# SCH_TRINIT_BYTE-HOGS_IOT_2023-02-12.net
KiCad netlist of a schematic drawn in EasyEDA
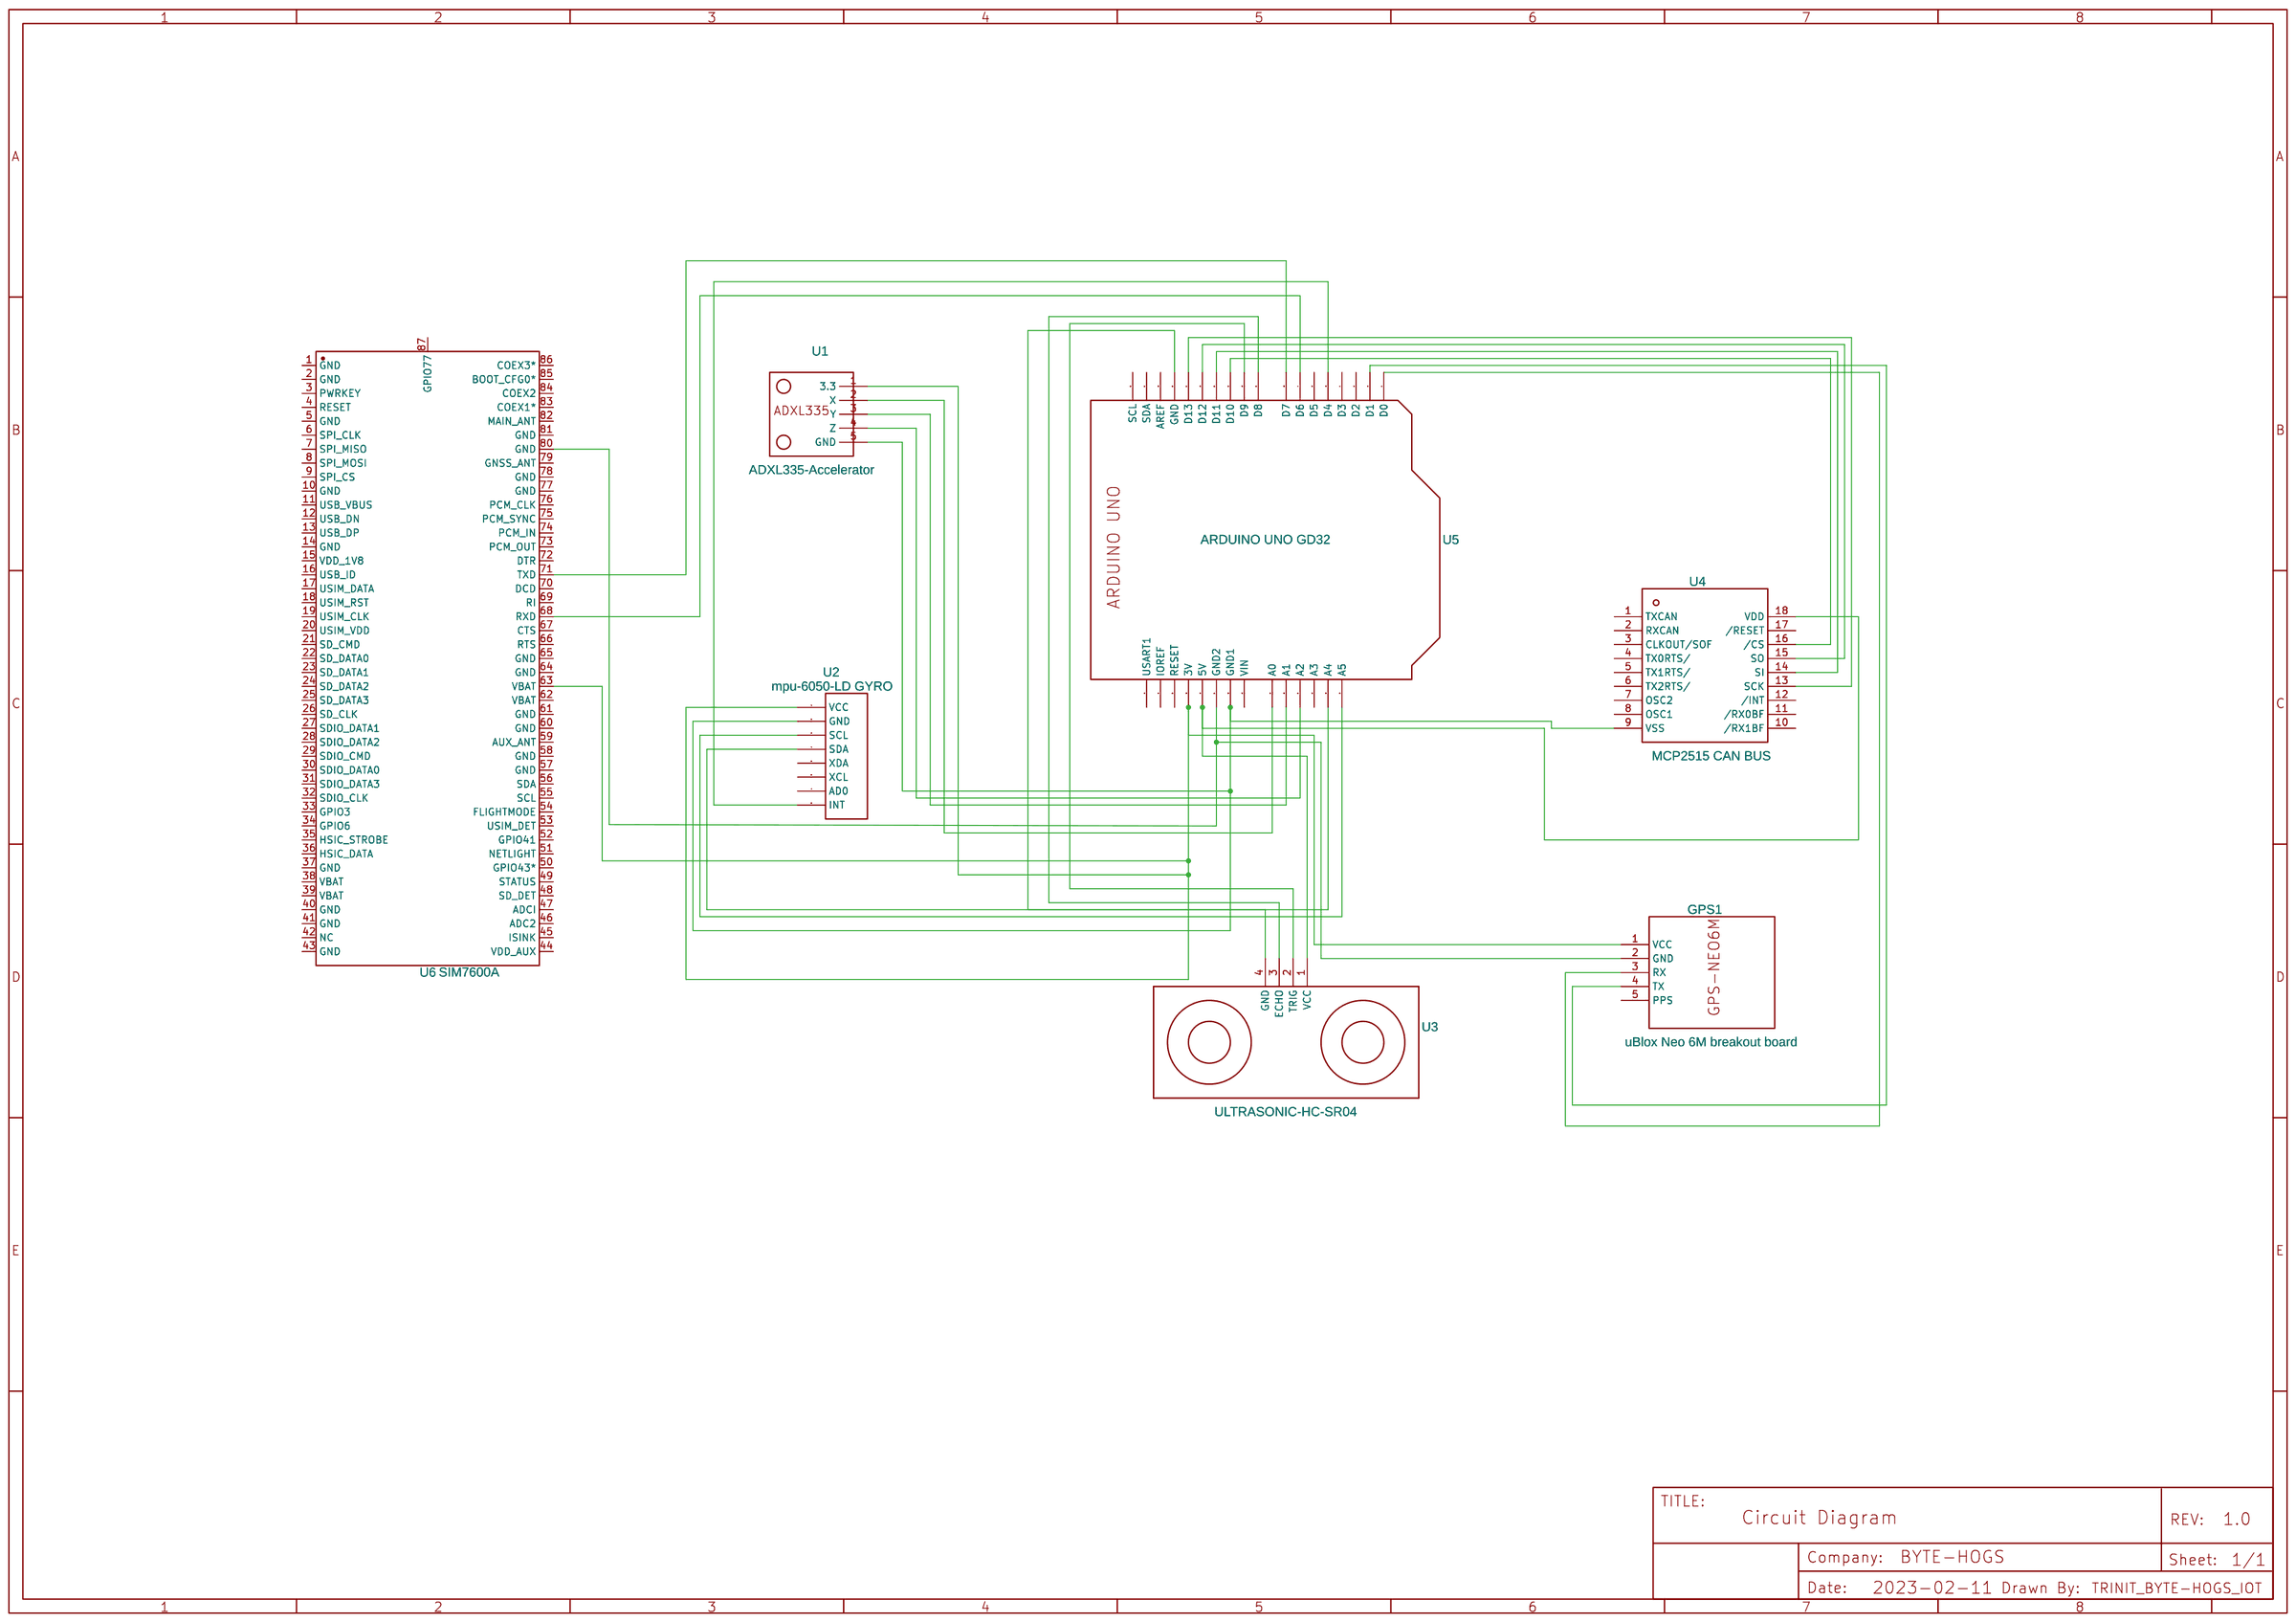
[diagram p0: schematic sheet]

(export (version "E")
  (design (tool "Eeschema 10.0.6"))
  (components
    (comp (ref "GPS1")
      (value "uBlox Neo 6M breakout board")
      (fields
        (field (name "BOM_Manufacturer Part") "GY-NEO6M")
        (field (name "BOM_Supplier Part") "GY-NEO6MV2")
      )
      (libsource (lib "") (part "uBlox Neo 6M breakout board"))
    )
    (comp (ref "U1")
      (value "ADXL335-Accelerator")
      (fields (field (name "BOM_Manufacturer Part") "ADXL335"))
      (libsource (lib "") (part "ADXL335"))
    )
    (comp (ref "U2") (value "mpu-6050-LD GYRO") (libsource (lib "") (part "mpu-6050-LD")))
    (comp (ref "U3") (value "ULTRASONIC-HC-SR04") (libsource (lib "") (part "ULTRASONIC-HC-SR04")))
    (comp (ref "U4") (value "MCP2515 CAN BUS") (libsource (lib "") (part "MCP2515 COPY")))
    (comp (ref "U5") (value "ARDUINO UNO GD32") (libsource (lib "") (part "ARDUINO UNO GD32")))
    (comp (ref "U6")
      (value "SIM7600A")
      (fields (field (name "BOM_Supplier Part") "C2995537"))
      (libsource (lib "") (part "SIM7600A"))
    )
  )
  (nets
    (net (code "1") (name "Net-(GPS1-GND)") (class "Default")
      (node (ref "GPS1") (pin "2") (pinfunction "GND_2") (pintype "unspecified"))
      (node (ref "U5") (pin "27") (pinfunction "GND2_27") (pintype "passive"))
      (node (ref "U6") (pin "80") (pinfunction "GND_80") (pintype "unspecified"))
    )
    (net (code "2") (name "Net-(GPS1-RX)") (class "Default")
      (node (ref "GPS1") (pin "3") (pinfunction "RX_3") (pintype "unspecified"))
      (node (ref "U5") (pin "1") (pinfunction "D0_1") (pintype "unspecified"))
    )
    (net (code "3") (name "Net-(GPS1-TX)") (class "Default")
      (node (ref "GPS1") (pin "4") (pinfunction "TX_4") (pintype "unspecified"))
      (node (ref "U5") (pin "2") (pinfunction "D1_2") (pintype "unspecified"))
    )
    (net (code "4") (name "Net-(GPS1-VCC)") (class "Default")
      (node (ref "GPS1") (pin "1") (pinfunction "VCC_1") (pintype "unspecified"))
      (node (ref "U1") (pin "1") (pinfunction "3.3_1") (pintype "unspecified"))
      (node (ref "U2") (pin "1") (pinfunction "VCC_1") (pintype "unspecified"))
      (node (ref "U5") (pin "29") (pinfunction "3V_29") (pintype "passive"))
      (node (ref "U6") (pin "63") (pinfunction "VBAT_63") (pintype "unspecified"))
    )
    (net (code "5") (name "Net-(U1-GND)") (class "Default")
      (node (ref "U1") (pin "5") (pinfunction "GND_5") (pintype "unspecified"))
      (node (ref "U2") (pin "2") (pinfunction "GND_2") (pintype "unspecified"))
      (node (ref "U4") (pin "9") (pinfunction "VSS_9") (pintype "unspecified"))
      (node (ref "U5") (pin "26") (pinfunction "GND1_26") (pintype "passive"))
    )
    (net (code "6") (name "Net-(U1-X)") (class "Default")
      (node (ref "U1") (pin "2") (pinfunction "X_2") (pintype "unspecified"))
      (node (ref "U5") (pin "24") (pinfunction "A0_24") (pintype "unspecified"))
    )
    (net (code "7") (name "Net-(U1-Y)") (class "Default")
      (node (ref "U1") (pin "3") (pinfunction "Y_3") (pintype "unspecified"))
      (node (ref "U5") (pin "23") (pinfunction "A1_23") (pintype "unspecified"))
    )
    (net (code "8") (name "Net-(U1-Z)") (class "Default")
      (node (ref "U1") (pin "4") (pinfunction "Z_4") (pintype "unspecified"))
      (node (ref "U5") (pin "22") (pinfunction "A2_22") (pintype "unspecified"))
    )
    (net (code "9") (name "Net-(U2-INT)") (class "Default")
      (node (ref "U2") (pin "8") (pinfunction "INT_8") (pintype "unspecified"))
      (node (ref "U5") (pin "5") (pinfunction "D4_5") (pintype "unspecified"))
    )
    (net (code "10") (name "Net-(U2-SCL)") (class "Default")
      (node (ref "U2") (pin "3") (pinfunction "SCL_3") (pintype "unspecified"))
      (node (ref "U5") (pin "19") (pinfunction "A5_19") (pintype "unspecified"))
    )
    (net (code "11") (name "Net-(U2-SDA)") (class "Default")
      (node (ref "U2") (pin "4") (pinfunction "SDA_4") (pintype "unspecified"))
      (node (ref "U5") (pin "20") (pinfunction "A4_20") (pintype "unspecified"))
    )
    (net (code "12") (name "Net-(U3-ECHO)") (class "Default")
      (node (ref "U3") (pin "3") (pinfunction "ECHO_3") (pintype "output"))
      (node (ref "U5") (pin "9") (pinfunction "D8_9") (pintype "unspecified"))
    )
    (net (code "13") (name "Net-(U3-GND)") (class "Default")
      (node (ref "U3") (pin "4") (pinfunction "GND_4") (pintype "passive"))
      (node (ref "U5") (pin "15") (pinfunction "GND_15") (pintype "passive"))
    )
    (net (code "14") (name "Net-(U3-TRIG)") (class "Default")
      (node (ref "U3") (pin "2") (pinfunction "TRIG_2") (pintype "input"))
      (node (ref "U5") (pin "10") (pinfunction "D9_10") (pintype "unspecified"))
    )
    (net (code "15") (name "Net-(U3-VCC)") (class "Default")
      (node (ref "U3") (pin "1") (pinfunction "VCC_1") (pintype "passive"))
      (node (ref "U4") (pin "18") (pinfunction "VDD_18") (pintype "unspecified"))
      (node (ref "U5") (pin "28") (pinfunction "5V_28") (pintype "passive"))
    )
    (net (code "16") (name "Net-(U4-SCK)") (class "Default")
      (node (ref "U4") (pin "13") (pinfunction "SCK_13") (pintype "unspecified"))
      (node (ref "U5") (pin "14") (pinfunction "D13_14") (pintype "unspecified"))
    )
    (net (code "17") (name "Net-(U4-SI)") (class "Default")
      (node (ref "U4") (pin "14") (pinfunction "SI_14") (pintype "unspecified"))
      (node (ref "U5") (pin "12") (pinfunction "D11_12") (pintype "unspecified"))
    )
    (net (code "18") (name "Net-(U4-SO)") (class "Default")
      (node (ref "U4") (pin "15") (pinfunction "SO_15") (pintype "unspecified"))
      (node (ref "U5") (pin "13") (pinfunction "D12_13") (pintype "unspecified"))
    )
    (net (code "19") (name "Net-(U4-{slash}CS)") (class "Default")
      (node (ref "U4") (pin "16") (pinfunction "/CS_16") (pintype "unspecified"))
      (node (ref "U5") (pin "11") (pinfunction "D10_11") (pintype "unspecified"))
    )
    (net (code "20") (name "Net-(U5-D6)") (class "Default")
      (node (ref "U5") (pin "7") (pinfunction "D6_7") (pintype "unspecified"))
      (node (ref "U6") (pin "68") (pinfunction "RXD_68") (pintype "unspecified"))
    )
    (net (code "21") (name "Net-(U5-D7)") (class "Default")
      (node (ref "U5") (pin "8") (pinfunction "D7_8") (pintype "unspecified"))
      (node (ref "U6") (pin "71") (pinfunction "TXD_71") (pintype "unspecified"))
    )
    (net (code "22") (name "unconnected-(GPS1-PPS-Pad5)") (class "Default")
      (node (ref "GPS1") (pin "5") (pinfunction "PPS_5") (pintype "unspecified"))
    )
    (net (code "23") (name "unconnected-(U2-AD0-Pad7)") (class "Default")
      (node (ref "U2") (pin "7") (pinfunction "AD0_7") (pintype "unspecified"))
    )
    (net (code "24") (name "unconnected-(U2-XCL-Pad6)") (class "Default")
      (node (ref "U2") (pin "6") (pinfunction "XCL_6") (pintype "unspecified"))
    )
    (net (code "25") (name "unconnected-(U2-XDA-Pad5)") (class "Default")
      (node (ref "U2") (pin "5") (pinfunction "XDA_5") (pintype "unspecified"))
    )
    (net (code "26") (name "unconnected-(U4-CLKOUT{slash}SOF-Pad3)") (class "Default")
      (node (ref "U4") (pin "3") (pinfunction "CLKOUT/SOF_3") (pintype "unspecified"))
    )
    (net (code "27") (name "unconnected-(U4-OSC1-Pad8)") (class "Default")
      (node (ref "U4") (pin "8") (pinfunction "OSC1_8") (pintype "unspecified"))
    )
    (net (code "28") (name "unconnected-(U4-OSC2-Pad7)") (class "Default")
      (node (ref "U4") (pin "7") (pinfunction "OSC2_7") (pintype "unspecified"))
    )
    (net (code "29") (name "unconnected-(U4-RXCAN-Pad2)") (class "Default")
      (node (ref "U4") (pin "2") (pinfunction "RXCAN_2") (pintype "unspecified"))
    )
    (net (code "30") (name "unconnected-(U4-TX0RTS{slash}-Pad4)") (class "Default")
      (node (ref "U4") (pin "4") (pinfunction "TX0RTS/_4") (pintype "unspecified"))
    )
    (net (code "31") (name "unconnected-(U4-TX1RTS{slash}-Pad5)") (class "Default")
      (node (ref "U4") (pin "5") (pinfunction "TX1RTS/_5") (pintype "unspecified"))
    )
    (net (code "32") (name "unconnected-(U4-TX2RTS{slash}-Pad6)") (class "Default")
      (node (ref "U4") (pin "6") (pinfunction "TX2RTS/_6") (pintype "unspecified"))
    )
    (net (code "33") (name "unconnected-(U4-TXCAN-Pad1)") (class "Default")
      (node (ref "U4") (pin "1") (pinfunction "TXCAN_1") (pintype "unspecified"))
    )
    (net (code "34") (name "unconnected-(U4-{slash}INT-Pad12)") (class "Default")
      (node (ref "U4") (pin "12") (pinfunction "/INT_12") (pintype "unspecified"))
    )
    (net (code "35") (name "unconnected-(U4-{slash}RESET-Pad17)") (class "Default")
      (node (ref "U4") (pin "17") (pinfunction "/RESET_17") (pintype "unspecified"))
    )
    (net (code "36") (name "unconnected-(U4-{slash}RX0BF-Pad11)") (class "Default")
      (node (ref "U4") (pin "11") (pinfunction "/RX0BF_11") (pintype "unspecified"))
    )
    (net (code "37") (name "unconnected-(U4-{slash}RX1BF-Pad10)") (class "Default")
      (node (ref "U4") (pin "10") (pinfunction "/RX1BF_10") (pintype "unspecified"))
    )
    (net (code "38") (name "unconnected-(U5-A3-Pad21)") (class "Default")
      (node (ref "U5") (pin "21") (pinfunction "A3_21") (pintype "unspecified"))
    )
    (net (code "39") (name "unconnected-(U5-AREF-Pad16)") (class "Default")
      (node (ref "U5") (pin "16") (pinfunction "AREF_16") (pintype "unspecified"))
    )
    (net (code "40") (name "unconnected-(U5-D2-Pad3)") (class "Default")
      (node (ref "U5") (pin "3") (pinfunction "D2_3") (pintype "unspecified"))
    )
    (net (code "41") (name "unconnected-(U5-D3-Pad4)") (class "Default")
      (node (ref "U5") (pin "4") (pinfunction "D3_4") (pintype "unspecified"))
    )
    (net (code "42") (name "unconnected-(U5-D5-Pad6)") (class "Default")
      (node (ref "U5") (pin "6") (pinfunction "D5_6") (pintype "unspecified"))
    )
    (net (code "43") (name "unconnected-(U5-IOREF-Pad31)") (class "Default")
      (node (ref "U5") (pin "31") (pinfunction "IOREF_31") (pintype "unspecified"))
    )
    (net (code "44") (name "unconnected-(U5-RESET-Pad30)") (class "Default")
      (node (ref "U5") (pin "30") (pinfunction "RESET_30") (pintype "unspecified"))
    )
    (net (code "45") (name "unconnected-(U5-SCL-Pad18)") (class "Default")
      (node (ref "U5") (pin "18") (pinfunction "SCL_18") (pintype "unspecified"))
    )
    (net (code "46") (name "unconnected-(U5-SDA-Pad17)") (class "Default")
      (node (ref "U5") (pin "17") (pinfunction "SDA_17") (pintype "unspecified"))
    )
    (net (code "47") (name "unconnected-(U5-USART1-Pad32)") (class "Default")
      (node (ref "U5") (pin "32") (pinfunction "USART1_32") (pintype "unspecified"))
    )
    (net (code "48") (name "unconnected-(U5-VIN-Pad25)") (class "Default")
      (node (ref "U5") (pin "25") (pinfunction "VIN_25") (pintype "passive"))
    )
    (net (code "49") (name "unconnected-(U6-ADC2-Pad46)") (class "Default")
      (node (ref "U6") (pin "46") (pinfunction "ADC2_46") (pintype "unspecified"))
    )
    (net (code "50") (name "unconnected-(U6-ADCI-Pad47)") (class "Default")
      (node (ref "U6") (pin "47") (pinfunction "ADCI_47") (pintype "unspecified"))
    )
    (net (code "51") (name "unconnected-(U6-AUX_ANT-Pad59)") (class "Default")
      (node (ref "U6") (pin "59") (pinfunction "AUX_ANT_59") (pintype "unspecified"))
    )
    (net (code "52") (name "unconnected-(U6-BOOT_CFG0*-Pad85)") (class "Default")
      (node (ref "U6") (pin "85") (pinfunction "BOOT_CFG0*_85") (pintype "unspecified"))
    )
    (net (code "53") (name "unconnected-(U6-COEX1*-Pad83)") (class "Default")
      (node (ref "U6") (pin "83") (pinfunction "COEX1*_83") (pintype "unspecified"))
    )
    (net (code "54") (name "unconnected-(U6-COEX2-Pad84)") (class "Default")
      (node (ref "U6") (pin "84") (pinfunction "COEX2_84") (pintype "unspecified"))
    )
    (net (code "55") (name "unconnected-(U6-COEX3*-Pad86)") (class "Default")
      (node (ref "U6") (pin "86") (pinfunction "COEX3*_86") (pintype "unspecified"))
    )
    (net (code "56") (name "unconnected-(U6-CTS-Pad67)") (class "Default")
      (node (ref "U6") (pin "67") (pinfunction "CTS_67") (pintype "unspecified"))
    )
    (net (code "57") (name "unconnected-(U6-DCD-Pad70)") (class "Default")
      (node (ref "U6") (pin "70") (pinfunction "DCD_70") (pintype "unspecified"))
    )
    (net (code "58") (name "unconnected-(U6-DTR-Pad72)") (class "Default")
      (node (ref "U6") (pin "72") (pinfunction "DTR_72") (pintype "unspecified"))
    )
    (net (code "59") (name "unconnected-(U6-FLIGHTMODE-Pad54)") (class "Default")
      (node (ref "U6") (pin "54") (pinfunction "FLIGHTMODE_54") (pintype "unspecified"))
    )
    (net (code "60") (name "unconnected-(U6-GND-Pad1)") (class "Default")
      (node (ref "U6") (pin "1") (pinfunction "GND_1") (pintype "unspecified"))
    )
    (net (code "61") (name "unconnected-(U6-GND-Pad2)") (class "Default")
      (node (ref "U6") (pin "2") (pinfunction "GND_2") (pintype "unspecified"))
    )
    (net (code "62") (name "unconnected-(U6-GND-Pad5)") (class "Default")
      (node (ref "U6") (pin "5") (pinfunction "GND_5") (pintype "unspecified"))
    )
    (net (code "63") (name "unconnected-(U6-GND-Pad10)") (class "Default")
      (node (ref "U6") (pin "10") (pinfunction "GND_10") (pintype "unspecified"))
    )
    (net (code "64") (name "unconnected-(U6-GND-Pad14)") (class "Default")
      (node (ref "U6") (pin "14") (pinfunction "GND_14") (pintype "unspecified"))
    )
    (net (code "65") (name "unconnected-(U6-GND-Pad37)") (class "Default")
      (node (ref "U6") (pin "37") (pinfunction "GND_37") (pintype "unspecified"))
    )
    (net (code "66") (name "unconnected-(U6-GND-Pad40)") (class "Default")
      (node (ref "U6") (pin "40") (pinfunction "GND_40") (pintype "unspecified"))
    )
    (net (code "67") (name "unconnected-(U6-GND-Pad41)") (class "Default")
      (node (ref "U6") (pin "41") (pinfunction "GND_41") (pintype "unspecified"))
    )
    (net (code "68") (name "unconnected-(U6-GND-Pad43)") (class "Default")
      (node (ref "U6") (pin "43") (pinfunction "GND_43") (pintype "unspecified"))
    )
    (net (code "69") (name "unconnected-(U6-GND-Pad57)") (class "Default")
      (node (ref "U6") (pin "57") (pinfunction "GND_57") (pintype "unspecified"))
    )
    (net (code "70") (name "unconnected-(U6-GND-Pad58)") (class "Default")
      (node (ref "U6") (pin "58") (pinfunction "GND_58") (pintype "unspecified"))
    )
    (net (code "71") (name "unconnected-(U6-GND-Pad60)") (class "Default")
      (node (ref "U6") (pin "60") (pinfunction "GND_60") (pintype "unspecified"))
    )
    (net (code "72") (name "unconnected-(U6-GND-Pad61)") (class "Default")
      (node (ref "U6") (pin "61") (pinfunction "GND_61") (pintype "unspecified"))
    )
    (net (code "73") (name "unconnected-(U6-GND-Pad64)") (class "Default")
      (node (ref "U6") (pin "64") (pinfunction "GND_64") (pintype "unspecified"))
    )
    (net (code "74") (name "unconnected-(U6-GND-Pad65)") (class "Default")
      (node (ref "U6") (pin "65") (pinfunction "GND_65") (pintype "unspecified"))
    )
    (net (code "75") (name "unconnected-(U6-GND-Pad77)") (class "Default")
      (node (ref "U6") (pin "77") (pinfunction "GND_77") (pintype "unspecified"))
    )
    (net (code "76") (name "unconnected-(U6-GND-Pad78)") (class "Default")
      (node (ref "U6") (pin "78") (pinfunction "GND_78") (pintype "unspecified"))
    )
    (net (code "77") (name "unconnected-(U6-GND-Pad81)") (class "Default")
      (node (ref "U6") (pin "81") (pinfunction "GND_81") (pintype "unspecified"))
    )
    (net (code "78") (name "unconnected-(U6-GNSS_ANT-Pad79)") (class "Default")
      (node (ref "U6") (pin "79") (pinfunction "GNSS_ANT_79") (pintype "unspecified"))
    )
    (net (code "79") (name "unconnected-(U6-GPIO3-Pad33)") (class "Default")
      (node (ref "U6") (pin "33") (pinfunction "GPIO3_33") (pintype "unspecified"))
    )
    (net (code "80") (name "unconnected-(U6-GPIO6-Pad34)") (class "Default")
      (node (ref "U6") (pin "34") (pinfunction "GPIO6_34") (pintype "unspecified"))
    )
    (net (code "81") (name "unconnected-(U6-GPIO41-Pad52)") (class "Default")
      (node (ref "U6") (pin "52") (pinfunction "GPIO41_52") (pintype "unspecified"))
    )
    (net (code "82") (name "unconnected-(U6-GPIO43*-Pad50)") (class "Default")
      (node (ref "U6") (pin "50") (pinfunction "GPIO43*_50") (pintype "unspecified"))
    )
    (net (code "83") (name "unconnected-(U6-GPIO77-Pad87)") (class "Default")
      (node (ref "U6") (pin "87") (pinfunction "GPIO77_87") (pintype "unspecified"))
    )
    (net (code "84") (name "unconnected-(U6-HSIC_DATA-Pad36)") (class "Default")
      (node (ref "U6") (pin "36") (pinfunction "HSIC_DATA_36") (pintype "unspecified"))
    )
    (net (code "85") (name "unconnected-(U6-HSIC_STROBE-Pad35)") (class "Default")
      (node (ref "U6") (pin "35") (pinfunction "HSIC_STROBE_35") (pintype "unspecified"))
    )
    (net (code "86") (name "unconnected-(U6-ISINK-Pad45)") (class "Default")
      (node (ref "U6") (pin "45") (pinfunction "ISINK_45") (pintype "unspecified"))
    )
    (net (code "87") (name "unconnected-(U6-MAIN_ANT-Pad82)") (class "Default")
      (node (ref "U6") (pin "82") (pinfunction "MAIN_ANT_82") (pintype "unspecified"))
    )
    (net (code "88") (name "unconnected-(U6-NC-Pad42)") (class "Default")
      (node (ref "U6") (pin "42") (pinfunction "NC_42") (pintype "unspecified"))
    )
    (net (code "89") (name "unconnected-(U6-NETLIGHT-Pad51)") (class "Default")
      (node (ref "U6") (pin "51") (pinfunction "NETLIGHT_51") (pintype "unspecified"))
    )
    (net (code "90") (name "unconnected-(U6-PCM_CLK-Pad76)") (class "Default")
      (node (ref "U6") (pin "76") (pinfunction "PCM_CLK_76") (pintype "unspecified"))
    )
    (net (code "91") (name "unconnected-(U6-PCM_IN-Pad74)") (class "Default")
      (node (ref "U6") (pin "74") (pinfunction "PCM_IN_74") (pintype "unspecified"))
    )
    (net (code "92") (name "unconnected-(U6-PCM_OUT-Pad73)") (class "Default")
      (node (ref "U6") (pin "73") (pinfunction "PCM_OUT_73") (pintype "unspecified"))
    )
    (net (code "93") (name "unconnected-(U6-PCM_SYNC-Pad75)") (class "Default")
      (node (ref "U6") (pin "75") (pinfunction "PCM_SYNC_75") (pintype "unspecified"))
    )
    (net (code "94") (name "unconnected-(U6-PWRKEY-Pad3)") (class "Default")
      (node (ref "U6") (pin "3") (pinfunction "PWRKEY_3") (pintype "unspecified"))
    )
    (net (code "95") (name "unconnected-(U6-RESET-Pad4)") (class "Default")
      (node (ref "U6") (pin "4") (pinfunction "RESET_4") (pintype "unspecified"))
    )
    (net (code "96") (name "unconnected-(U6-RI-Pad69)") (class "Default")
      (node (ref "U6") (pin "69") (pinfunction "RI_69") (pintype "unspecified"))
    )
    (net (code "97") (name "unconnected-(U6-RTS-Pad66)") (class "Default")
      (node (ref "U6") (pin "66") (pinfunction "RTS_66") (pintype "unspecified"))
    )
    (net (code "98") (name "unconnected-(U6-SCL-Pad55)") (class "Default")
      (node (ref "U6") (pin "55") (pinfunction "SCL_55") (pintype "unspecified"))
    )
    (net (code "99") (name "unconnected-(U6-SDA-Pad56)") (class "Default")
      (node (ref "U6") (pin "56") (pinfunction "SDA_56") (pintype "unspecified"))
    )
    (net (code "100") (name "unconnected-(U6-SDIO_CLK-Pad32)") (class "Default")
      (node (ref "U6") (pin "32") (pinfunction "SDIO_CLK_32") (pintype "unspecified"))
    )
    (net (code "101") (name "unconnected-(U6-SDIO_CMD-Pad29)") (class "Default")
      (node (ref "U6") (pin "29") (pinfunction "SDIO_CMD_29") (pintype "unspecified"))
    )
    (net (code "102") (name "unconnected-(U6-SDIO_DATA0-Pad30)") (class "Default")
      (node (ref "U6") (pin "30") (pinfunction "SDIO_DATA0_30") (pintype "unspecified"))
    )
    (net (code "103") (name "unconnected-(U6-SDIO_DATA1-Pad27)") (class "Default")
      (node (ref "U6") (pin "27") (pinfunction "SDIO_DATA1_27") (pintype "unspecified"))
    )
    (net (code "104") (name "unconnected-(U6-SDIO_DATA2-Pad28)") (class "Default")
      (node (ref "U6") (pin "28") (pinfunction "SDIO_DATA2_28") (pintype "unspecified"))
    )
    (net (code "105") (name "unconnected-(U6-SDIO_DATA3-Pad31)") (class "Default")
      (node (ref "U6") (pin "31") (pinfunction "SDIO_DATA3_31") (pintype "unspecified"))
    )
    (net (code "106") (name "unconnected-(U6-SD_CLK-Pad26)") (class "Default")
      (node (ref "U6") (pin "26") (pinfunction "SD_CLK_26") (pintype "unspecified"))
    )
    (net (code "107") (name "unconnected-(U6-SD_CMD-Pad21)") (class "Default")
      (node (ref "U6") (pin "21") (pinfunction "SD_CMD_21") (pintype "unspecified"))
    )
    (net (code "108") (name "unconnected-(U6-SD_DATA0-Pad22)") (class "Default")
      (node (ref "U6") (pin "22") (pinfunction "SD_DATA0_22") (pintype "unspecified"))
    )
    (net (code "109") (name "unconnected-(U6-SD_DATA1-Pad23)") (class "Default")
      (node (ref "U6") (pin "23") (pinfunction "SD_DATA1_23") (pintype "unspecified"))
    )
    (net (code "110") (name "unconnected-(U6-SD_DATA2-Pad24)") (class "Default")
      (node (ref "U6") (pin "24") (pinfunction "SD_DATA2_24") (pintype "unspecified"))
    )
    (net (code "111") (name "unconnected-(U6-SD_DATA3-Pad25)") (class "Default")
      (node (ref "U6") (pin "25") (pinfunction "SD_DATA3_25") (pintype "unspecified"))
    )
    (net (code "112") (name "unconnected-(U6-SD_DET-Pad48)") (class "Default")
      (node (ref "U6") (pin "48") (pinfunction "SD_DET_48") (pintype "unspecified"))
    )
    (net (code "113") (name "unconnected-(U6-SPI_CLK-Pad6)") (class "Default")
      (node (ref "U6") (pin "6") (pinfunction "SPI_CLK_6") (pintype "unspecified"))
    )
    (net (code "114") (name "unconnected-(U6-SPI_CS-Pad9)") (class "Default")
      (node (ref "U6") (pin "9") (pinfunction "SPI_CS_9") (pintype "unspecified"))
    )
    (net (code "115") (name "unconnected-(U6-SPI_MISO-Pad7)") (class "Default")
      (node (ref "U6") (pin "7") (pinfunction "SPI_MISO_7") (pintype "unspecified"))
    )
    (net (code "116") (name "unconnected-(U6-SPI_MOSI-Pad8)") (class "Default")
      (node (ref "U6") (pin "8") (pinfunction "SPI_MOSI_8") (pintype "unspecified"))
    )
    (net (code "117") (name "unconnected-(U6-STATUS-Pad49)") (class "Default")
      (node (ref "U6") (pin "49") (pinfunction "STATUS_49") (pintype "unspecified"))
    )
    (net (code "118") (name "unconnected-(U6-USB_DN-Pad12)") (class "Default")
      (node (ref "U6") (pin "12") (pinfunction "USB_DN_12") (pintype "unspecified"))
    )
    (net (code "119") (name "unconnected-(U6-USB_DP-Pad13)") (class "Default")
      (node (ref "U6") (pin "13") (pinfunction "USB_DP_13") (pintype "unspecified"))
    )
    (net (code "120") (name "unconnected-(U6-USB_ID-Pad16)") (class "Default")
      (node (ref "U6") (pin "16") (pinfunction "USB_ID_16") (pintype "unspecified"))
    )
    (net (code "121") (name "unconnected-(U6-USB_VBUS-Pad11)") (class "Default")
      (node (ref "U6") (pin "11") (pinfunction "USB_VBUS_11") (pintype "unspecified"))
    )
    (net (code "122") (name "unconnected-(U6-USIM_CLK-Pad19)") (class "Default")
      (node (ref "U6") (pin "19") (pinfunction "USIM_CLK_19") (pintype "unspecified"))
    )
    (net (code "123") (name "unconnected-(U6-USIM_DATA-Pad17)") (class "Default")
      (node (ref "U6") (pin "17") (pinfunction "USIM_DATA_17") (pintype "unspecified"))
    )
    (net (code "124") (name "unconnected-(U6-USIM_DET-Pad53)") (class "Default")
      (node (ref "U6") (pin "53") (pinfunction "USIM_DET_53") (pintype "unspecified"))
    )
    (net (code "125") (name "unconnected-(U6-USIM_RST-Pad18)") (class "Default")
      (node (ref "U6") (pin "18") (pinfunction "USIM_RST_18") (pintype "unspecified"))
    )
    (net (code "126") (name "unconnected-(U6-USIM_VDD-Pad20)") (class "Default")
      (node (ref "U6") (pin "20") (pinfunction "USIM_VDD_20") (pintype "unspecified"))
    )
    (net (code "127") (name "unconnected-(U6-VBAT-Pad38)") (class "Default")
      (node (ref "U6") (pin "38") (pinfunction "VBAT_38") (pintype "unspecified"))
    )
    (net (code "128") (name "unconnected-(U6-VBAT-Pad39)") (class "Default")
      (node (ref "U6") (pin "39") (pinfunction "VBAT_39") (pintype "unspecified"))
    )
    (net (code "129") (name "unconnected-(U6-VBAT-Pad62)") (class "Default")
      (node (ref "U6") (pin "62") (pinfunction "VBAT_62") (pintype "unspecified"))
    )
    (net (code "130") (name "unconnected-(U6-VDD_1V8-Pad15)") (class "Default")
      (node (ref "U6") (pin "15") (pinfunction "VDD_1V8_15") (pintype "unspecified"))
    )
    (net (code "131") (name "unconnected-(U6-VDD_AUX-Pad44)") (class "Default")
      (node (ref "U6") (pin "44") (pinfunction "VDD_AUX_44") (pintype "unspecified"))
    )
  )
)
